# 09B-10.net
KiCad netlist of a schematic drawn in EAGLE
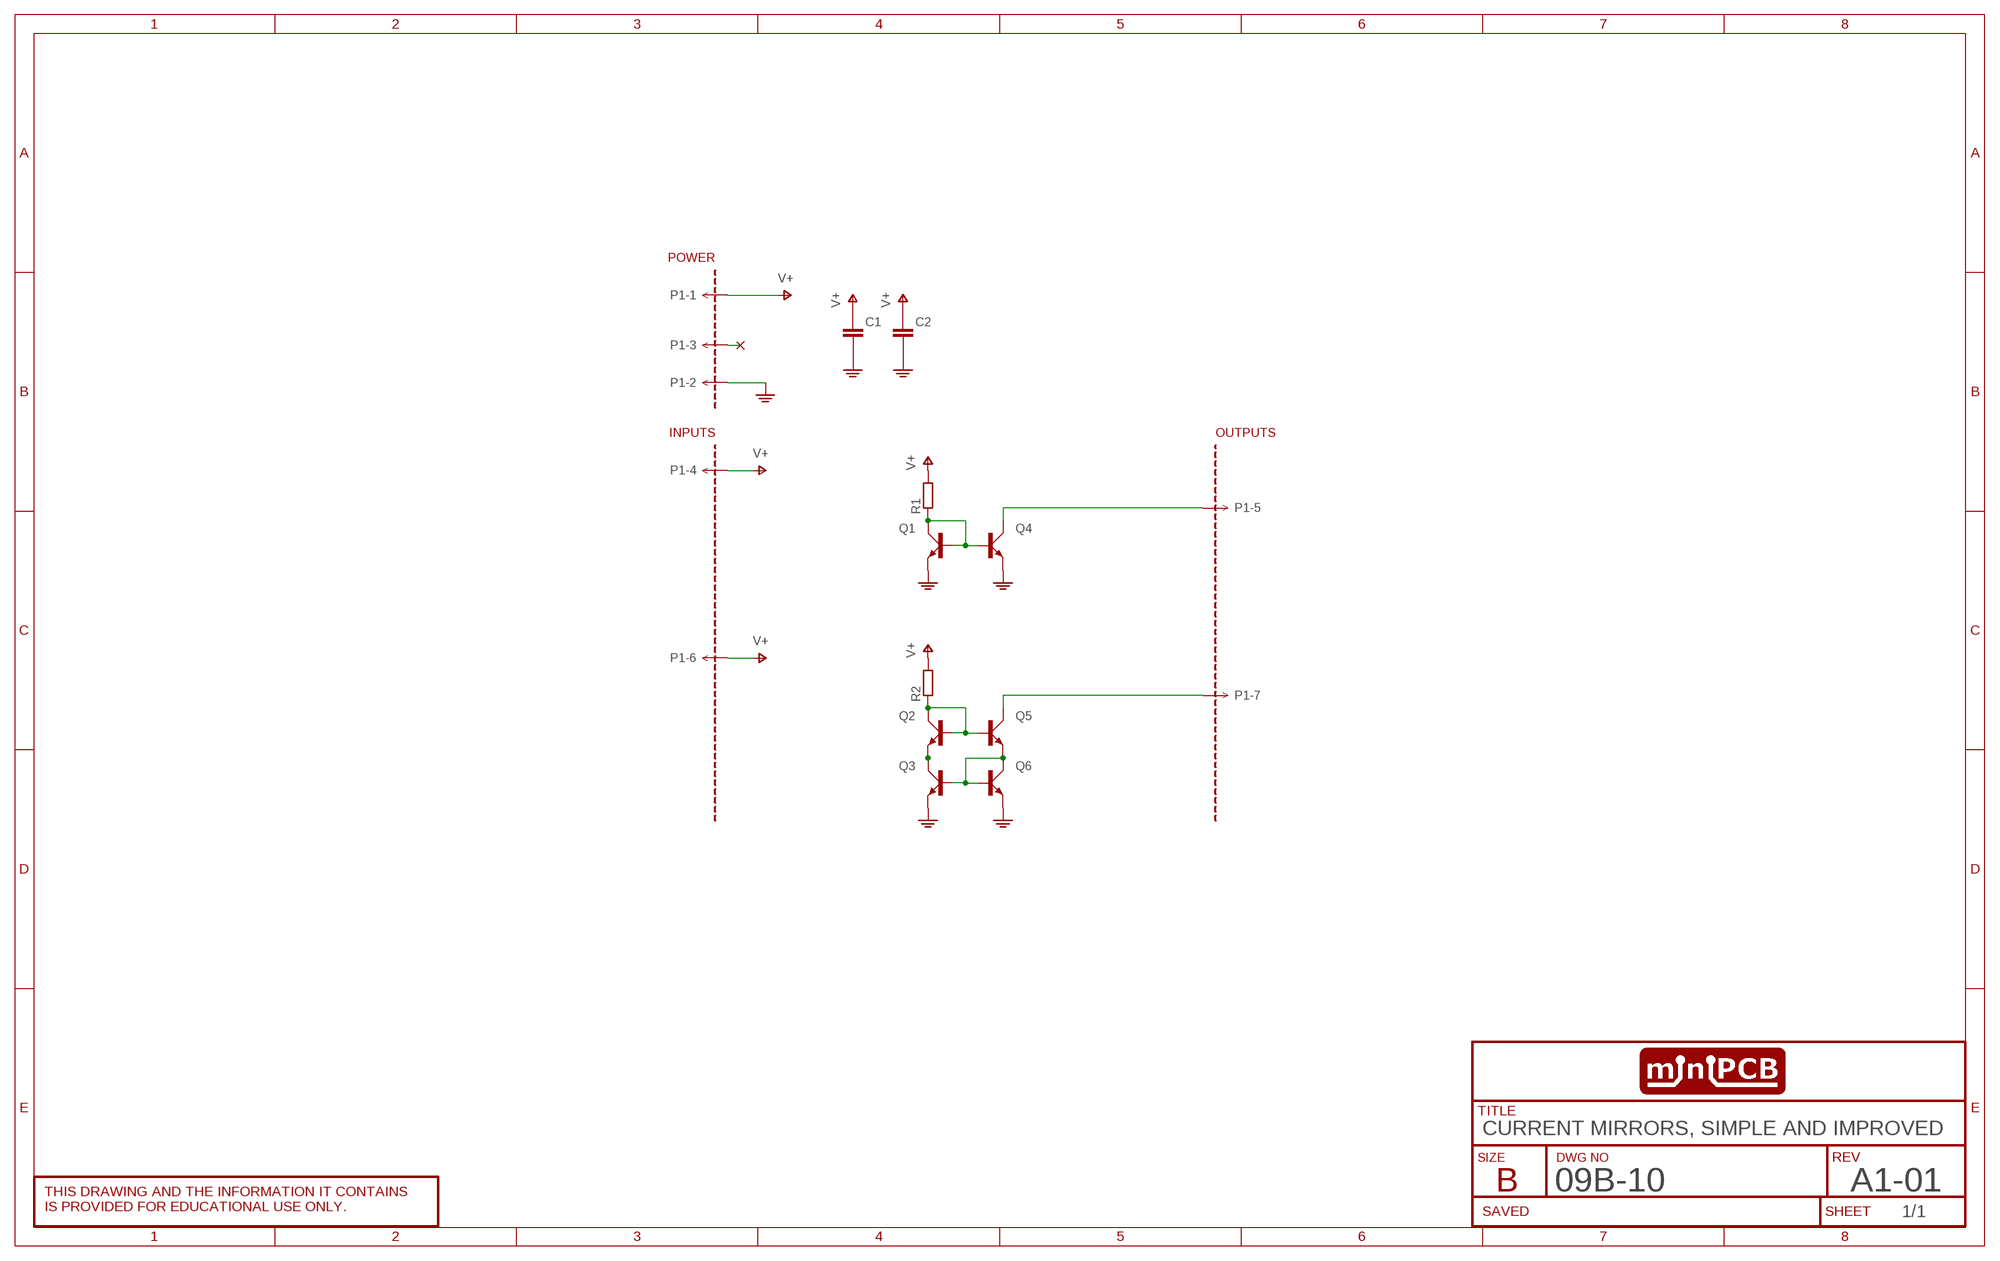
[diagram p0: schematic, sheet 1]

(export (version "E")
  (design (tool "Eeschema 10.0.6"))
  (components
    (comp (ref "C1")
      (value "CAPACITORSMD")
      (footprint "eagle-import:C0805")
      (libsource (lib "eagle-import") (part "CAPACITORSMD"))
    )
    (comp (ref "C2")
      (value "CAPACITORSMD")
      (footprint "eagle-import:C0805")
      (libsource (lib "eagle-import") (part "CAPACITORSMD"))
    )
    (comp (ref "P1")
      (value "MINIPCB_7P")
      (footprint "eagle-import:PINS_1X7")
      (libsource (lib "eagle-import") (part "MINIPCB_7P"))
    )
    (comp (ref "PCB1")
      (value "MINIPCB_0PPCB33")
      (footprint "eagle-import:PCB33")
      (fields (field (name "PART_NUMBER") "09B-10") (field (name "TITLE") "CURRENT MIRRORS"))
      (libsource (lib "eagle-import") (part "MINIPCB_0PPCB33"))
    )
    (comp (ref "Q1")
      (value "BJT_NPNBEC")
      (footprint "eagle-import:SOT23")
      (libsource (lib "eagle-import") (part "BJT_NPNBEC"))
    )
    (comp (ref "Q2")
      (value "BJT_NPNBEC")
      (footprint "eagle-import:SOT23")
      (libsource (lib "eagle-import") (part "BJT_NPNBEC"))
    )
    (comp (ref "Q3")
      (value "BJT_NPNBEC")
      (footprint "eagle-import:SOT23")
      (libsource (lib "eagle-import") (part "BJT_NPNBEC"))
    )
    (comp (ref "Q4")
      (value "BJT_NPNBEC")
      (footprint "eagle-import:SOT23")
      (libsource (lib "eagle-import") (part "BJT_NPNBEC"))
    )
    (comp (ref "Q5")
      (value "BJT_NPNBEC")
      (footprint "eagle-import:SOT23")
      (libsource (lib "eagle-import") (part "BJT_NPNBEC"))
    )
    (comp (ref "Q6")
      (value "BJT_NPNBEC")
      (footprint "eagle-import:SOT23")
      (libsource (lib "eagle-import") (part "BJT_NPNBEC"))
    )
    (comp (ref "R1")
      (value "RESISTORSMD")
      (footprint "eagle-import:R0805")
      (libsource (lib "eagle-import") (part "RESISTORSMD"))
    )
    (comp (ref "R2")
      (value "RESISTORSMD")
      (footprint "eagle-import:R0805")
      (libsource (lib "eagle-import") (part "RESISTORSMD"))
    )
  )
  (nets
    (net (code "1") (name "GND") (class "Default")
      (node (ref "C1") (pin "2ASDF") (pinfunction "-_2ASDF") (pintype "passive"))
      (node (ref "C2") (pin "2ASDF") (pinfunction "-_2ASDF") (pintype "passive"))
      (node (ref "P1") (pin "2") (pinfunction "1_2") (pintype "bidirectional"))
      (node (ref "Q1") (pin "2") (pinfunction "E_2") (pintype "passive"))
      (node (ref "Q3") (pin "2") (pinfunction "E_2") (pintype "passive"))
      (node (ref "Q4") (pin "2") (pinfunction "E_2") (pintype "passive"))
      (node (ref "Q6") (pin "2") (pinfunction "E_2") (pintype "passive"))
    )
    (net (code "2") (name "Net-(P1E-1)") (class "Default")
      (node (ref "P1") (pin "5") (pinfunction "1_5") (pintype "bidirectional"))
      (node (ref "Q4") (pin "3") (pinfunction "C_3") (pintype "passive"))
    )
    (net (code "3") (name "Net-(P1G-1)") (class "Default")
      (node (ref "P1") (pin "7") (pinfunction "1_7") (pintype "bidirectional"))
      (node (ref "Q5") (pin "3") (pinfunction "C_3") (pintype "passive"))
    )
    (net (code "4") (name "Net-(Q1-B)") (class "Default")
      (node (ref "Q1") (pin "1") (pinfunction "B_1") (pintype "passive"))
      (node (ref "Q1") (pin "3") (pinfunction "C_3") (pintype "passive"))
      (node (ref "Q4") (pin "1") (pinfunction "B_1") (pintype "passive"))
      (node (ref "R1") (pin "1") (pinfunction "1_1") (pintype "passive"))
    )
    (net (code "5") (name "Net-(Q2-B)") (class "Default")
      (node (ref "Q2") (pin "1") (pinfunction "B_1") (pintype "passive"))
      (node (ref "Q2") (pin "3") (pinfunction "C_3") (pintype "passive"))
      (node (ref "Q5") (pin "1") (pinfunction "B_1") (pintype "passive"))
      (node (ref "R2") (pin "1") (pinfunction "1_1") (pintype "passive"))
    )
    (net (code "6") (name "Net-(Q2-E)") (class "Default")
      (node (ref "Q2") (pin "2") (pinfunction "E_2") (pintype "passive"))
      (node (ref "Q3") (pin "3") (pinfunction "C_3") (pintype "passive"))
    )
    (net (code "7") (name "Net-(Q3-B)") (class "Default")
      (node (ref "Q3") (pin "1") (pinfunction "B_1") (pintype "passive"))
      (node (ref "Q5") (pin "2") (pinfunction "E_2") (pintype "passive"))
      (node (ref "Q6") (pin "1") (pinfunction "B_1") (pintype "passive"))
      (node (ref "Q6") (pin "3") (pinfunction "C_3") (pintype "passive"))
    )
    (net (code "8") (name "V+") (class "Default")
      (node (ref "C1") (pin "1ASD") (pinfunction "+_1ASD") (pintype "passive"))
      (node (ref "C2") (pin "1ASD") (pinfunction "+_1ASD") (pintype "passive"))
      (node (ref "P1") (pin "1") (pinfunction "1_1") (pintype "bidirectional"))
      (node (ref "P1") (pin "4") (pinfunction "1_4") (pintype "bidirectional"))
      (node (ref "P1") (pin "6") (pinfunction "1_6") (pintype "bidirectional"))
      (node (ref "R1") (pin "2") (pinfunction "2_2") (pintype "passive"))
      (node (ref "R2") (pin "2") (pinfunction "2_2") (pintype "passive"))
    )
    (net (code "9") (name "unconnected-(P1C-1-Pad3)") (class "Default")
      (node (ref "P1") (pin "3") (pinfunction "1_3") (pintype "bidirectional"))
    )
  )
)
